# output.net
KiCad netlist of a schematic drawn in EAGLE
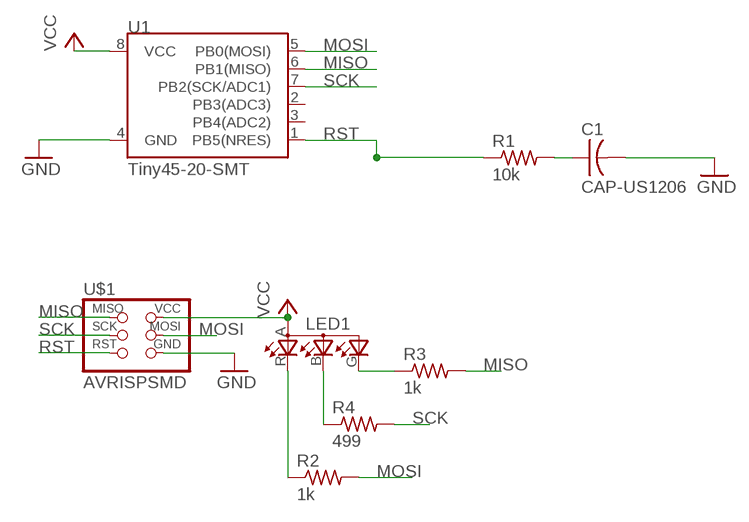
[diagram p0: schematic, sheet 1]

(export (version "E")
  (design (tool "Eeschema 10.0.6"))
  (components
    (comp (ref "C1")
      (value "CAP-US1206")
      (footprint "eagle-import:C1206")
      (libsource (lib "eagle-import") (part "CAP-US1206"))
    )
    (comp (ref "LED1")
      (value "LEDRGBOLD")
      (footprint "eagle-import:P-LCC-4-3")
      (libsource (lib "eagle-import") (part "LEDRGBOLD"))
    )
    (comp (ref "R1")
      (value "10k")
      (footprint "eagle-import:M1206")
      (libsource (lib "eagle-import") (part "R-US_M1206"))
    )
    (comp (ref "R2")
      (value "1k")
      (footprint "eagle-import:M1206")
      (libsource (lib "eagle-import") (part "R-US_M1206"))
    )
    (comp (ref "R3")
      (value "1k")
      (footprint "eagle-import:M1206")
      (libsource (lib "eagle-import") (part "R-US_M1206"))
    )
    (comp (ref "R4")
      (value "499")
      (footprint "eagle-import:M1206")
      (libsource (lib "eagle-import") (part "R-US_M1206"))
    )
    (comp (ref "U$1")
      (value "AVRISPSMD")
      (footprint "eagle-import:2X03SMD")
      (libsource (lib "eagle-import") (part "AVRISPSMD"))
    )
    (comp (ref "U1")
      (value "Tiny45-20-SMT")
      (footprint "eagle-import:SO08-EIAJ")
      (libsource (lib "eagle-import") (part "ATTINY45TINY45-20-SMT"))
    )
  )
  (nets
    (net (code "1") (name "/MISO") (class "Default")
      (node (ref "R3") (pin "2") (pinfunction "2_2") (pintype "passive"))
      (node (ref "U$1") (pin "1") (pinfunction "MISO_1") (pintype "passive"))
      (node (ref "U1") (pin "6") (pinfunction "PB1(MISO)_6") (pintype "bidirectional"))
    )
    (net (code "2") (name "/MOSI") (class "Default")
      (node (ref "R2") (pin "2") (pinfunction "2_2") (pintype "passive"))
      (node (ref "U$1") (pin "4") (pinfunction "MOSI_4") (pintype "passive"))
      (node (ref "U1") (pin "5") (pinfunction "PB0(MOSI)_5") (pintype "bidirectional"))
    )
    (net (code "3") (name "/RST") (class "Default")
      (node (ref "R1") (pin "1") (pinfunction "1_1") (pintype "passive"))
      (node (ref "U$1") (pin "5") (pinfunction "RST_5") (pintype "passive"))
      (node (ref "U1") (pin "1") (pinfunction "PB5(NRES)_1") (pintype "bidirectional"))
    )
    (net (code "4") (name "/SCK") (class "Default")
      (node (ref "R4") (pin "2") (pinfunction "2_2") (pintype "passive"))
      (node (ref "U$1") (pin "3") (pinfunction "SCK_3") (pintype "passive"))
      (node (ref "U1") (pin "7") (pinfunction "PB2(SCK/ADC1)_7") (pintype "bidirectional"))
    )
    (net (code "5") (name "GND") (class "Default")
      (node (ref "C1") (pin "2") (pinfunction "2_2") (pintype "passive"))
      (node (ref "U$1") (pin "6") (pinfunction "GND_6") (pintype "passive"))
      (node (ref "U1") (pin "4") (pinfunction "GND_4") (pintype "bidirectional"))
    )
    (net (code "6") (name "Net-(C1-Pad1)") (class "Default")
      (node (ref "C1") (pin "1") (pinfunction "1_1") (pintype "passive"))
      (node (ref "R1") (pin "2") (pinfunction "2_2") (pintype "passive"))
    )
    (net (code "7") (name "Net-(LED1-CBLUE)") (class "Default")
      (node (ref "LED1") (pin "B") (pinfunction "CBLUE_B") (pintype "passive"))
      (node (ref "R4") (pin "1") (pinfunction "1_1") (pintype "passive"))
    )
    (net (code "8") (name "Net-(LED1-CGREEN)") (class "Default")
      (node (ref "LED1") (pin "G") (pinfunction "CGREEN_G") (pintype "passive"))
      (node (ref "R3") (pin "1") (pinfunction "1_1") (pintype "passive"))
    )
    (net (code "9") (name "Net-(LED1-CRED)") (class "Default")
      (node (ref "LED1") (pin "R") (pinfunction "CRED_R") (pintype "passive"))
      (node (ref "R2") (pin "1") (pinfunction "1_1") (pintype "passive"))
    )
    (net (code "10") (name "VCC") (class "Default")
      (node (ref "LED1") (pin "A") (pinfunction "A2_A") (pintype "passive"))
      (node (ref "U$1") (pin "2") (pinfunction "VCC_2") (pintype "passive"))
      (node (ref "U1") (pin "8") (pinfunction "VCC_8") (pintype "bidirectional"))
    )
    (net (code "11") (name "unconnected-(U1-PB3(ADC3)-Pad2)") (class "Default")
      (node (ref "U1") (pin "2") (pinfunction "PB3(ADC3)_2") (pintype "bidirectional"))
    )
    (net (code "12") (name "unconnected-(U1-PB4(ADC2)-Pad3)") (class "Default")
      (node (ref "U1") (pin "3") (pinfunction "PB4(ADC2)_3") (pintype "bidirectional"))
    )
  )
)
